# Supply.net
KiCad netlist of a schematic drawn in Altium Designer
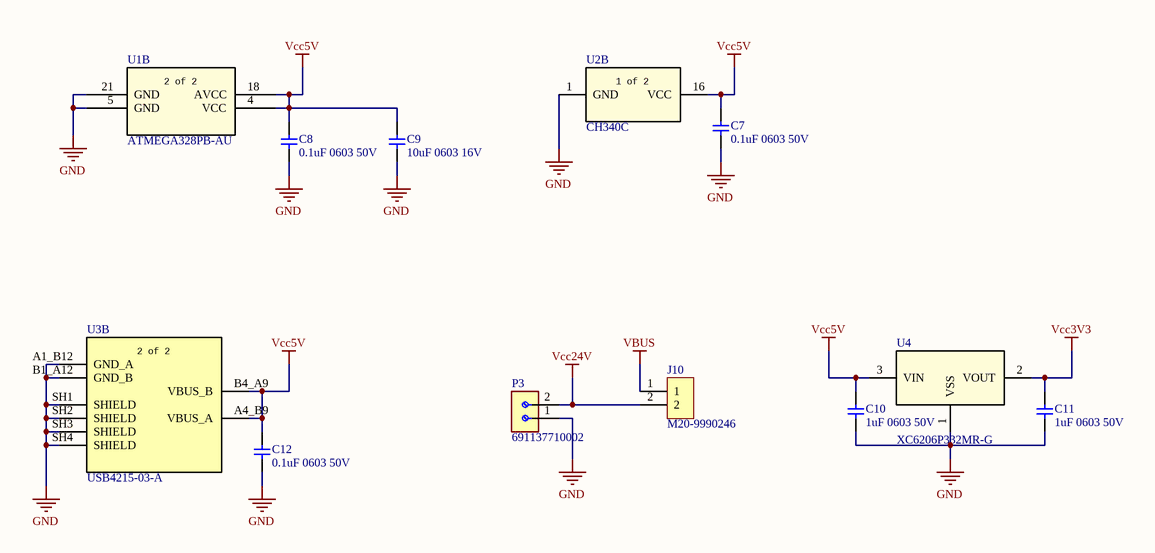
[diagram p0: Supply.SchDoc]

(export (version "E")
  (design (tool "Eeschema 10.0.6"))
  (components
    (comp (ref "C7")
      (value "0.1uF 0603 50V")
      (footprint "CAP_0603")
      (description "50V 0.1uF (100nF) X7R ±10% 0603 Multilayer Ceramic Capacitors MLCC - SMD/SMT ROHS")
      (fields
        (field (name "MANUFACTURER PART NUMBER") "CL10B104KB8NNNC")
        (field (name "JLCPCB PART NUMBER") "C1591")
      )
      (libsource (lib "Amperry") (part "Capacitor"))
    )
    (comp (ref "C8")
      (value "0.1uF 0603 50V")
      (footprint "CAP_0603")
      (description "50V 0.1uF (100nF) X7R ±10% 0603 Multilayer Ceramic Capacitors MLCC - SMD/SMT ROHS")
      (fields
        (field (name "MANUFACTURER PART NUMBER") "CL10B104KB8NNNC")
        (field (name "JLCPCB PART NUMBER") "C1591")
      )
      (libsource (lib "Amperry") (part "Capacitor"))
    )
    (comp (ref "C9")
      (value "10uF 0603 16V")
      (footprint "CAP_0603")
      (description "6.3V 10uF X5R ±20% 0603 Multilayer Ceramic Capacitors MLCC - SMD/SMT ROHS")
      (fields (field (name "MANUFACTURER") "Samsung Electro-Mechanics") (field (name "VOLTAGE") "6.3V"))
      (libsource (lib "Amperry") (part "Capacitor"))
    )
    (comp (ref "C10")
      (value "1uF 0603 50V")
      (footprint "CAP_0603")
      (description "50V 1uF X5R ±10% 0603 Multilayer Ceramic Capacitors MLCC - SMD/SMT ROHS")
      (fields (field (name "MANUFACTURER") "Samsung Electro-Mechanics") (field (name "TOLERANCE") "10%"))
      (libsource (lib "Amperry") (part "Capacitor"))
    )
    (comp (ref "C11")
      (value "1uF 0603 50V")
      (footprint "CAP_0603")
      (description "50V 1uF X5R ±10% 0603 Multilayer Ceramic Capacitors MLCC - SMD/SMT ROHS")
      (fields (field (name "MANUFACTURER") "Samsung Electro-Mechanics") (field (name "TOLERANCE") "10%"))
      (libsource (lib "Amperry") (part "Capacitor"))
    )
    (comp (ref "C12")
      (value "0.1uF 0603 50V")
      (footprint "CAP_0603")
      (description "50V 0.1uF (100nF) X7R ±10% 0603 Multilayer Ceramic Capacitors MLCC - SMD/SMT ROHS")
      (fields
        (field (name "MANUFACTURER PART NUMBER") "CL10B104KB8NNNC")
        (field (name "JLCPCB PART NUMBER") "C1591")
      )
      (libsource (lib "Amperry") (part "Capacitor"))
    )
    (comp (ref "J10")
      (value "M20-9990246")
      (footprint "Header_Male_1x2_2.54mm")
      (description "Header Male 1x2 2.54mm")
      (fields (field (name "JLCPCB PART NUMBER") "C90288") (field (name "MANUFACTURER") "Harwin"))
      (libsource (lib "Amperry") (part "Header_Male_1x2"))
    )
    (comp (ref "P3")
      (value "691137710002")
      (footprint "Termina_Block_1x2_5mm")
      (description "Terminal Block, 5mm Pitch, Horizontal, Pressure Clamp Glow Wire, Pcb, 2PINS, Gr")
      (fields (field (name "MANUFACTURER") "Wurth Elektronik") (field (name "JLCPCB PART NUMBER") "C3703"))
      (libsource (lib "Amperry") (part "Terminal_Block_1x2"))
    )
    (comp (ref "U1")
      (value "ATMEGA328PB-AU")
      (footprint "TQFP-32")
      (fields
        (field (name "JLCPCB PART NUMBER") "C618731")
        (field (name "COPYRIGHT") "Copyright (C) 2025 Ultra Librarian. All rights reserved.")
      )
      (libsource (lib "Amperry") (part "ATMEGA328PB-AU"))
    )
    (comp (ref "U2")
      (value "CH340C")
      (footprint "SOP-16")
      (description "USB to UART Serial Converter")
      (fields (field (name "JLCPCB PART NUMBER") "C84681"))
      (libsource (lib "Amperry") (part "CH340C"))
    )
    (comp (ref "U3")
      (value "USB4215-03-A")
      (footprint "USB4215-03-A")
      (description "USB-C, 12+4 Contacts 16POS Rohs Compliant: Yes")
      (fields
        (field (name "JLCPCB PART NUMBER") "C165948")
        (field (name "MANUFACTURER") "Global Connector Technology")
      )
      (libsource (lib "Amperry") (part "USB-C 16P"))
    )
    (comp (ref "U4")
      (value "XC6206P332MR-G")
      (footprint "SOT-23-3")
      (description "LDO 3.3V 200mA")
      (fields (field (name "MANUFACTURER") "Torex") (field (name "JLCPCB PART NUMBER") "C5446"))
      (libsource (lib "Amperry") (part "XC6206P332MR-G"))
    )
  )
  (nets
    (net (code "1") (name "GND") (class "Default")
      (node (ref "C10") (pin "1") (pinfunction "1_1") (pintype "passive"))
      (node (ref "C11") (pin "1") (pinfunction "1_1") (pintype "passive"))
      (node (ref "C12") (pin "1") (pinfunction "1_1") (pintype "passive"))
      (node (ref "C7") (pin "1") (pinfunction "1_1") (pintype "passive"))
      (node (ref "C8") (pin "1") (pinfunction "1_1") (pintype "passive"))
      (node (ref "C9") (pin "1") (pinfunction "1_1") (pintype "passive"))
      (node (ref "P3") (pin "1") (pinfunction "1_1") (pintype "passive"))
      (node (ref "U1") (pin "21") (pinfunction "GND_21") (pintype "power_in"))
      (node (ref "U1") (pin "5") (pinfunction "GND_5") (pintype "power_in"))
      (node (ref "U2") (pin "1") (pinfunction "GND_1") (pintype "power_in"))
      (node (ref "U3") (pin "A1_B12") (pinfunction "GND_A_A1_B12") (pintype "power_in"))
      (node (ref "U3") (pin "B1_A12") (pinfunction "GND_B_B1_A12") (pintype "power_in"))
      (node (ref "U3") (pin "SH1") (pinfunction "SHIELD_SH1") (pintype "passive"))
      (node (ref "U3") (pin "SH2") (pinfunction "SHIELD_SH2") (pintype "passive"))
      (node (ref "U3") (pin "SH3") (pinfunction "SHIELD_SH3") (pintype "passive"))
      (node (ref "U3") (pin "SH4") (pinfunction "SHIELD_SH4") (pintype "passive"))
      (node (ref "U4") (pin "1") (pinfunction "VSS_1") (pintype "passive"))
    )
    (net (code "2") (name "VBUS") (class "Default")
      (node (ref "J10") (pin "1") (pinfunction "1_1") (pintype "passive"))
    )
    (net (code "3") (name "Vcc3V3") (class "Default")
      (node (ref "C11") (pin "2") (pinfunction "2_2") (pintype "passive"))
      (node (ref "U4") (pin "2") (pinfunction "VOUT_2") (pintype "passive"))
    )
    (net (code "4") (name "Vcc5V") (class "Default")
      (node (ref "C10") (pin "2") (pinfunction "2_2") (pintype "passive"))
      (node (ref "C12") (pin "2") (pinfunction "2_2") (pintype "passive"))
      (node (ref "C7") (pin "2") (pinfunction "2_2") (pintype "passive"))
      (node (ref "C8") (pin "2") (pinfunction "2_2") (pintype "passive"))
      (node (ref "C9") (pin "2") (pinfunction "2_2") (pintype "passive"))
      (node (ref "U1") (pin "18") (pinfunction "AVCC_18") (pintype "power_in"))
      (node (ref "U1") (pin "4") (pinfunction "VCC_4") (pintype "power_in"))
      (node (ref "U2") (pin "16") (pinfunction "VCC_16") (pintype "passive"))
      (node (ref "U3") (pin "A4_B9") (pinfunction "VBUS_A_A4_B9") (pintype "power_in"))
      (node (ref "U3") (pin "B4_A9") (pinfunction "VBUS_B_B4_A9") (pintype "power_in"))
      (node (ref "U4") (pin "3") (pinfunction "VIN_3") (pintype "passive"))
    )
    (net (code "5") (name "Vcc24V") (class "Default")
      (node (ref "J10") (pin "2") (pinfunction "2_2") (pintype "passive"))
      (node (ref "P3") (pin "2") (pinfunction "2_2") (pintype "passive"))
    )
  )
)
